# keyfinal.net
KiCad netlist of a schematic drawn in EAGLE
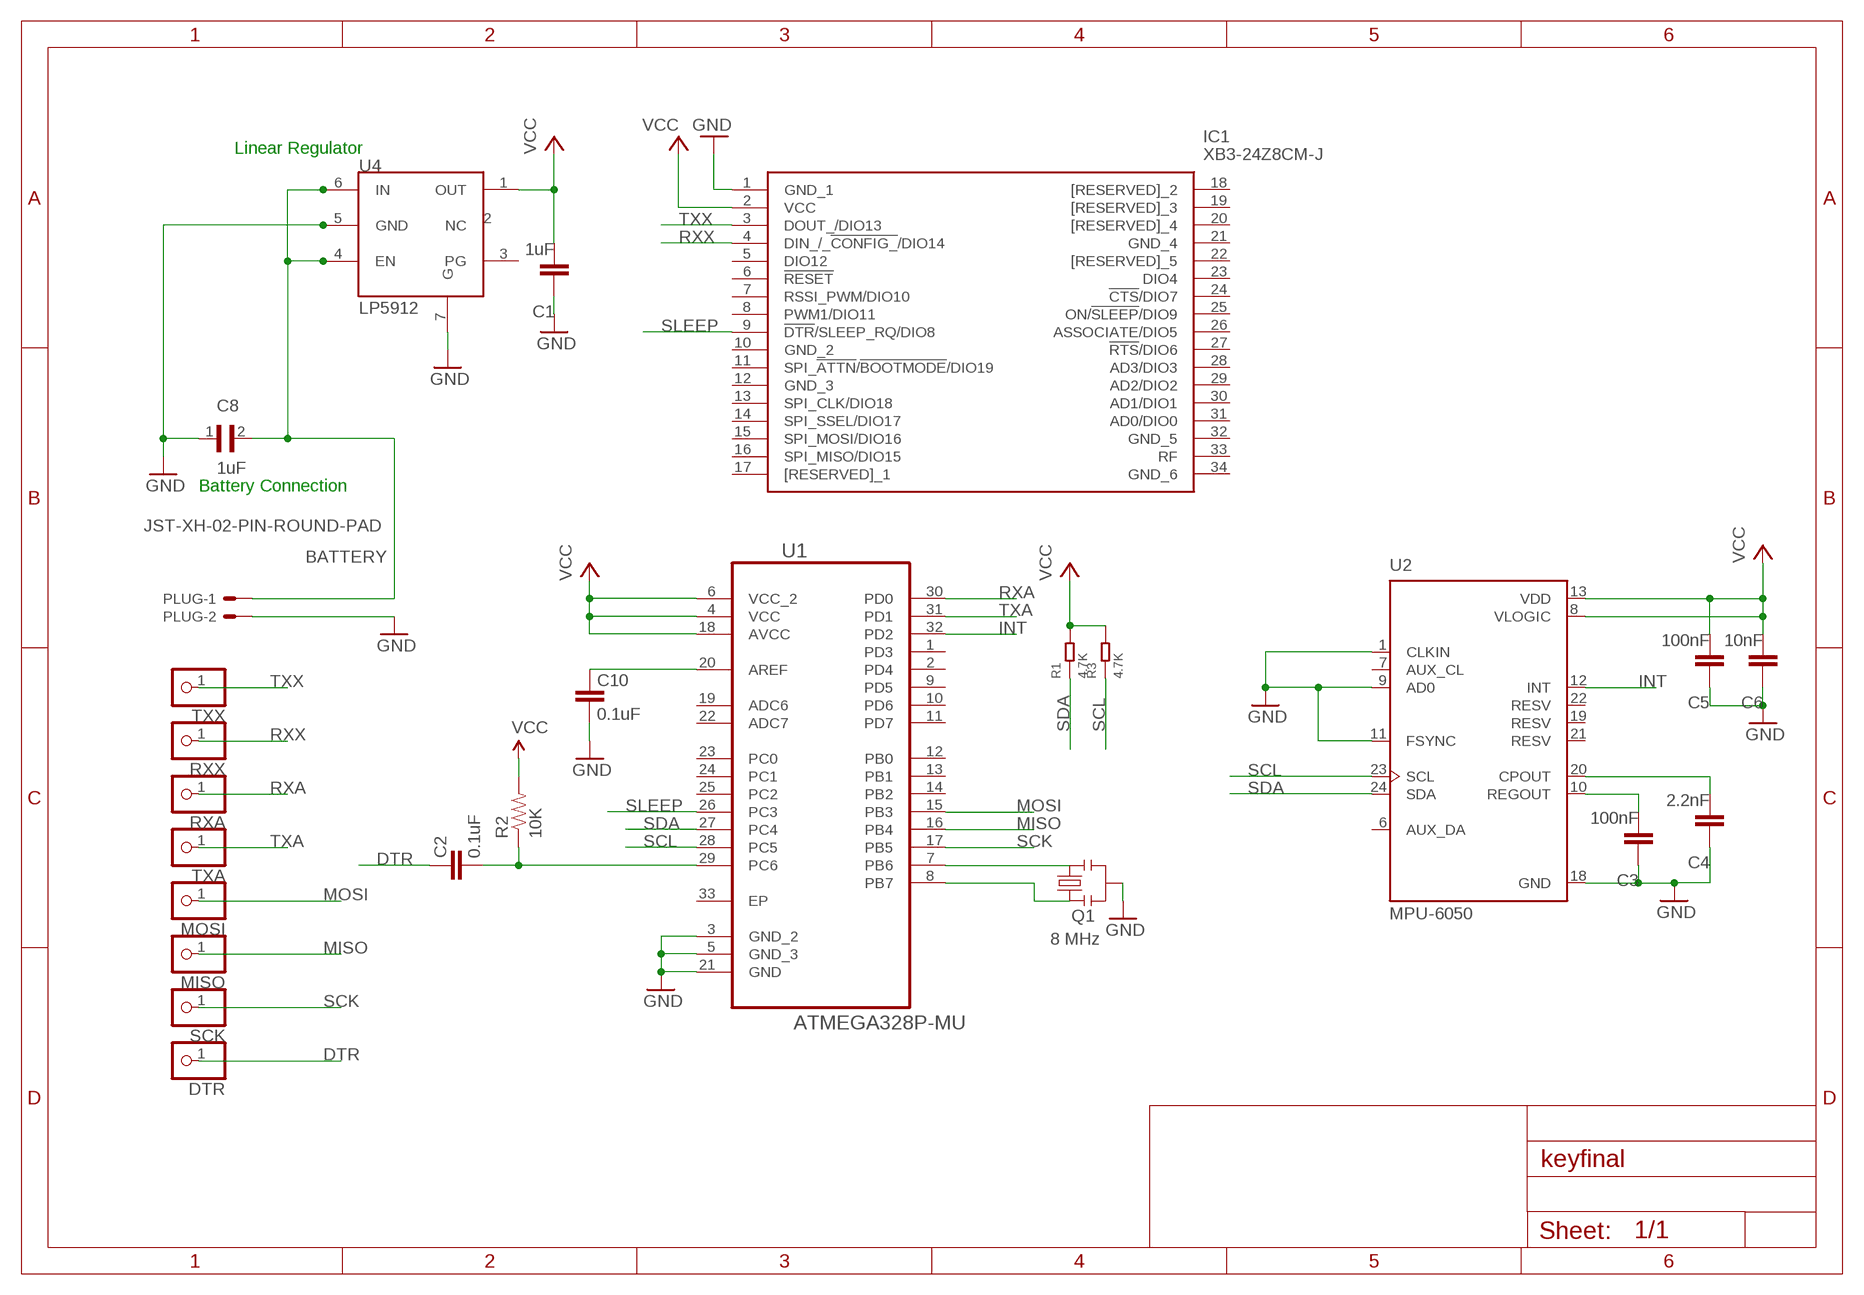
[diagram p0: schematic, sheet 1]

(export (version "E")
  (design (tool "Eeschema 10.0.6"))
  (components
    (comp (ref "C1")
      (value "1uF")
      (footprint "eagle-import:C0603")
      (libsource (lib "eagle-import") (part "C-EUC0603"))
    )
    (comp (ref "C2")
      (value "0.1uF")
      (footprint "eagle-import:0603-CAP")
      (libsource (lib "eagle-import") (part "CAP0603-CAP"))
    )
    (comp (ref "C3")
      (value "100nF")
      (footprint "eagle-import:C0603")
      (libsource (lib "eagle-import") (part "C-EUC0603"))
    )
    (comp (ref "C4")
      (value "2.2nF")
      (footprint "eagle-import:C0603")
      (libsource (lib "eagle-import") (part "C-EUC0603"))
    )
    (comp (ref "C5")
      (value "100nF")
      (footprint "eagle-import:C0603")
      (libsource (lib "eagle-import") (part "C-EUC0603"))
    )
    (comp (ref "C6")
      (value "10nF")
      (footprint "eagle-import:C0603")
      (libsource (lib "eagle-import") (part "C-EUC0603"))
    )
    (comp (ref "C8")
      (value "1uF")
      (footprint "eagle-import:CAPC1005X71N")
      (fields (field (name "MF") "AVX") (field (name "MP") "0402YD105MAT2A"))
      (libsource (lib "eagle-import") (part "0402YD105MAT2A"))
    )
    (comp (ref "C10")
      (value "0.1uF")
      (footprint "eagle-import:0603-CAP")
      (libsource (lib "eagle-import") (part "CAP0603-CAP"))
    )
    (comp (ref "DTR")
      (value "DTR")
      (footprint "eagle-import:1X01")
      (libsource (lib "eagle-import") (part "PINHD-1X1"))
    )
    (comp (ref "IC1")
      (value "XB3-24Z8CM-J")
      (footprint "eagle-import:XB324Z8CMJ")
      (fields (field (name "MOUSER_PART_NUMBER") "888-XB3-24Z8CM-J"))
      (libsource (lib "eagle-import") (part "XB3-24Z8CM-J"))
    )
    (comp (ref "MISO")
      (value "PINHD-1X1")
      (footprint "eagle-import:1X01")
      (libsource (lib "eagle-import") (part "PINHD-1X1"))
    )
    (comp (ref "MOSI")
      (value "PINHD-1X1")
      (footprint "eagle-import:1X01")
      (libsource (lib "eagle-import") (part "PINHD-1X1"))
    )
    (comp (ref "PLUG")
      (value "JST-XH-02-PIN-ROUND-PAD")
      (footprint "eagle-import:JST-XH-02-PACKAGE-ROUND-PAD")
      (libsource (lib "eagle-import") (part "JST-XH-02-PIN-ROUND-PAD"))
    )
    (comp (ref "Q1")
      (value "8 MHz")
      (footprint "eagle-import:RESONATOR-SMD-1_1")
      (libsource (lib "eagle-import") (part "RESONATOR1{colon}1"))
    )
    (comp (ref "R1")
      (value "4.7K")
      (footprint "eagle-import:R0402")
      (fields (field (name "MF") "Yageo") (field (name "MP") "RC0402JR074K7L"))
      (libsource (lib "eagle-import") (part "SMD-RES-4.7K-5%-1/16W(0402)"))
    )
    (comp (ref "R2")
      (value "10K")
      (footprint "eagle-import:0603-RES")
      (libsource (lib "eagle-import") (part "RESISTOR0603-RES"))
    )
    (comp (ref "R3")
      (value "4.7K")
      (footprint "eagle-import:R0402")
      (fields (field (name "MF") "Yageo") (field (name "MP") "RC0402JR074K7L"))
      (libsource (lib "eagle-import") (part "SMD-RES-4.7K-5%-1/16W(0402)"))
    )
    (comp (ref "RXA")
      (value "PINHD-1X1")
      (footprint "eagle-import:1X01")
      (libsource (lib "eagle-import") (part "PINHD-1X1"))
    )
    (comp (ref "RXX")
      (value "PINHD-1X1")
      (footprint "eagle-import:1X01")
      (libsource (lib "eagle-import") (part "PINHD-1X1"))
    )
    (comp (ref "SCK")
      (value "PINHD-1X1")
      (footprint "eagle-import:1X01")
      (fields (field (name "SPICEPREFIX") "X"))
      (libsource (lib "eagle-import") (part "PINHD-1X1"))
    )
    (comp (ref "TXA")
      (value "PINHD-1X1")
      (footprint "eagle-import:1X01")
      (libsource (lib "eagle-import") (part "PINHD-1X1"))
    )
    (comp (ref "TXX")
      (value "PINHD-1X1")
      (footprint "eagle-import:1X01")
      (libsource (lib "eagle-import") (part "PINHD-1X1"))
    )
    (comp (ref "U1")
      (value "ATMEGA328P-MU")
      (footprint "eagle-import:QFN50P500X500X100-33N")
      (fields (field (name "MF") "Microchip"))
      (libsource (lib "eagle-import") (part "ATMEGA328P-MU"))
    )
    (comp (ref "U2")
      (value "MPU-6050")
      (footprint "eagle-import:QFN50P400X400X95-24N")
      (fields (field (name "MF") "TDK InvenSense"))
      (libsource (lib "eagle-import") (part "MPU-6050"))
    )
    (comp (ref "U4")
      (value "LP5912")
      (footprint "eagle-import:LP5912")
      (libsource (lib "eagle-import") (part "LP5912"))
    )
  )
  (nets
    (net (code "1") (name "/BATTERY") (class "Default")
      (node (ref "C8") (pin "2") (pinfunction "2_2") (pintype "passive"))
      (node (ref "PLUG") (pin "1") (pinfunction "S_1") (pintype "passive"))
      (node (ref "U4") (pin "4") (pinfunction "EN_4") (pintype "bidirectional"))
      (node (ref "U4") (pin "6") (pinfunction "IN_6") (pintype "power_in"))
    )
    (net (code "2") (name "/DTR") (class "Default")
      (node (ref "C2") (pin "2") (pinfunction "2_2") (pintype "passive"))
      (node (ref "DTR") (pin "1") (pinfunction "1_1") (pintype "passive"))
    )
    (net (code "3") (name "/INT") (class "Default")
      (node (ref "U1") (pin "32") (pinfunction "PD2_32") (pintype "bidirectional"))
      (node (ref "U2") (pin "12") (pinfunction "INT_12") (pintype "output"))
    )
    (net (code "4") (name "/MISO") (class "Default")
      (node (ref "MISO") (pin "1") (pinfunction "1_1") (pintype "passive"))
      (node (ref "U1") (pin "16") (pinfunction "PB4_16") (pintype "bidirectional"))
    )
    (net (code "5") (name "/MOSI") (class "Default")
      (node (ref "MOSI") (pin "1") (pinfunction "1_1") (pintype "passive"))
      (node (ref "U1") (pin "15") (pinfunction "PB3_15") (pintype "bidirectional"))
    )
    (net (code "6") (name "/RXA") (class "Default")
      (node (ref "RXA") (pin "1") (pinfunction "1_1") (pintype "passive"))
      (node (ref "U1") (pin "30") (pinfunction "PD0_30") (pintype "bidirectional"))
    )
    (net (code "7") (name "/RXX") (class "Default")
      (node (ref "IC1") (pin "4") (pinfunction "DIN_/_~{CONFIG_}/DIO14_4") (pintype "bidirectional"))
      (node (ref "RXX") (pin "1") (pinfunction "1_1") (pintype "passive"))
    )
    (net (code "8") (name "/SCK") (class "Default")
      (node (ref "SCK") (pin "1") (pinfunction "1_1") (pintype "passive"))
      (node (ref "U1") (pin "17") (pinfunction "PB5_17") (pintype "bidirectional"))
    )
    (net (code "9") (name "/SCL") (class "Default")
      (node (ref "R3") (pin "1") (pinfunction "1_1") (pintype "passive"))
      (node (ref "U1") (pin "28") (pinfunction "PC5_28") (pintype "bidirectional"))
      (node (ref "U2") (pin "23") (pinfunction "SCL_23") (pintype "input"))
    )
    (net (code "10") (name "/SDA") (class "Default")
      (node (ref "R1") (pin "1") (pinfunction "1_1") (pintype "passive"))
      (node (ref "U1") (pin "27") (pinfunction "PC4_27") (pintype "bidirectional"))
      (node (ref "U2") (pin "24") (pinfunction "SDA_24") (pintype "bidirectional"))
    )
    (net (code "11") (name "/SLEEP") (class "Default")
      (node (ref "IC1") (pin "9") (pinfunction "~{DTR}/SLEEP_RQ/DIO8_9") (pintype "bidirectional"))
      (node (ref "U1") (pin "26") (pinfunction "PC3_26") (pintype "bidirectional"))
    )
    (net (code "12") (name "/TXA") (class "Default")
      (node (ref "TXA") (pin "1") (pinfunction "1_1") (pintype "passive"))
      (node (ref "U1") (pin "31") (pinfunction "PD1_31") (pintype "bidirectional"))
    )
    (net (code "13") (name "/TXX") (class "Default")
      (node (ref "IC1") (pin "3") (pinfunction "DOUT_/DIO13_3") (pintype "bidirectional"))
      (node (ref "TXX") (pin "1") (pinfunction "1_1") (pintype "passive"))
    )
    (net (code "14") (name "GND") (class "Default")
      (node (ref "C1") (pin "1") (pinfunction "1_1") (pintype "passive"))
      (node (ref "C10") (pin "1") (pinfunction "1_1") (pintype "passive"))
      (node (ref "C3") (pin "1") (pinfunction "1_1") (pintype "passive"))
      (node (ref "C4") (pin "1") (pinfunction "1_1") (pintype "passive"))
      (node (ref "C5") (pin "1") (pinfunction "1_1") (pintype "passive"))
      (node (ref "C6") (pin "1") (pinfunction "1_1") (pintype "passive"))
      (node (ref "C8") (pin "1") (pinfunction "1_1") (pintype "passive"))
      (node (ref "IC1") (pin "1") (pinfunction "GND_1_1") (pintype "bidirectional"))
      (node (ref "PLUG") (pin "2") (pinfunction "S_2") (pintype "passive"))
      (node (ref "Q1") (pin "2") (pinfunction "2_2") (pintype "passive"))
      (node (ref "U1") (pin "21") (pinfunction "GND_21") (pintype "passive"))
      (node (ref "U1") (pin "3") (pinfunction "GND_2_3") (pintype "passive"))
      (node (ref "U1") (pin "5") (pinfunction "GND_3_5") (pintype "passive"))
      (node (ref "U2") (pin "1") (pinfunction "CLKIN_1") (pintype "input"))
      (node (ref "U2") (pin "11") (pinfunction "FSYNC_11") (pintype "input"))
      (node (ref "U2") (pin "18") (pinfunction "GND_18") (pintype "power_in"))
      (node (ref "U2") (pin "9") (pinfunction "AD0_9") (pintype "input"))
      (node (ref "U4") (pin "5") (pinfunction "GND_5") (pintype "power_in"))
      (node (ref "U4") (pin "7") (pinfunction "G_7") (pintype "bidirectional"))
    )
    (net (code "15") (name "Net-(U1-AREF)") (class "Default")
      (node (ref "C10") (pin "2") (pinfunction "2_2") (pintype "passive"))
      (node (ref "U1") (pin "20") (pinfunction "AREF_20") (pintype "input"))
    )
    (net (code "16") (name "Net-(U1-PB6)") (class "Default")
      (node (ref "Q1") (pin "3") (pinfunction "3_3") (pintype "passive"))
      (node (ref "U1") (pin "7") (pinfunction "PB6_7") (pintype "bidirectional"))
    )
    (net (code "17") (name "Net-(U1-PB7)") (class "Default")
      (node (ref "Q1") (pin "1") (pinfunction "1_1") (pintype "passive"))
      (node (ref "U1") (pin "8") (pinfunction "PB7_8") (pintype "bidirectional"))
    )
    (net (code "18") (name "Net-(U1-PC6)") (class "Default")
      (node (ref "C2") (pin "1") (pinfunction "1_1") (pintype "passive"))
      (node (ref "R2") (pin "1") (pinfunction "1_1") (pintype "passive"))
      (node (ref "U1") (pin "29") (pinfunction "PC6_29") (pintype "bidirectional"))
    )
    (net (code "19") (name "Net-(U2-CPOUT)") (class "Default")
      (node (ref "C4") (pin "2") (pinfunction "2_2") (pintype "passive"))
      (node (ref "U2") (pin "20") (pinfunction "CPOUT_20") (pintype "passive"))
    )
    (net (code "20") (name "Net-(U2-REGOUT)") (class "Default")
      (node (ref "C3") (pin "2") (pinfunction "2_2") (pintype "passive"))
      (node (ref "U2") (pin "10") (pinfunction "REGOUT_10") (pintype "passive"))
    )
    (net (code "21") (name "VCC") (class "Default")
      (node (ref "C1") (pin "2") (pinfunction "2_2") (pintype "passive"))
      (node (ref "C5") (pin "2") (pinfunction "2_2") (pintype "passive"))
      (node (ref "C6") (pin "2") (pinfunction "2_2") (pintype "passive"))
      (node (ref "IC1") (pin "2") (pinfunction "VCC_2") (pintype "bidirectional"))
      (node (ref "R1") (pin "2") (pinfunction "2_2") (pintype "passive"))
      (node (ref "R2") (pin "2") (pinfunction "2_2") (pintype "passive"))
      (node (ref "R3") (pin "2") (pinfunction "2_2") (pintype "passive"))
      (node (ref "U1") (pin "18") (pinfunction "AVCC_18") (pintype "power_in"))
      (node (ref "U1") (pin "4") (pinfunction "VCC_4") (pintype "power_in"))
      (node (ref "U1") (pin "6") (pinfunction "VCC_2_6") (pintype "power_in"))
      (node (ref "U2") (pin "13") (pinfunction "VDD_13") (pintype "power_in"))
      (node (ref "U2") (pin "8") (pinfunction "VLOGIC_8") (pintype "power_in"))
      (node (ref "U4") (pin "1") (pinfunction "OUT_1") (pintype "power_in"))
    )
    (net (code "22") (name "unconnected-(IC1-AD0{slash}DIO0-Pad31)") (class "Default")
      (node (ref "IC1") (pin "31") (pinfunction "AD0/DIO0_31") (pintype "bidirectional"))
    )
    (net (code "23") (name "unconnected-(IC1-AD1{slash}DIO1-Pad30)") (class "Default")
      (node (ref "IC1") (pin "30") (pinfunction "AD1/DIO1_30") (pintype "bidirectional"))
    )
    (net (code "24") (name "unconnected-(IC1-AD2{slash}DIO2-Pad29)") (class "Default")
      (node (ref "IC1") (pin "29") (pinfunction "AD2/DIO2_29") (pintype "bidirectional"))
    )
    (net (code "25") (name "unconnected-(IC1-AD3{slash}DIO3-Pad28)") (class "Default")
      (node (ref "IC1") (pin "28") (pinfunction "AD3/DIO3_28") (pintype "bidirectional"))
    )
    (net (code "26") (name "unconnected-(IC1-ASSOCIATE{slash}DIO5-Pad26)") (class "Default")
      (node (ref "IC1") (pin "26") (pinfunction "ASSOCIATE/DIO5_26") (pintype "bidirectional"))
    )
    (net (code "27") (name "unconnected-(IC1-DIO4-Pad23)") (class "Default")
      (node (ref "IC1") (pin "23") (pinfunction "DIO4_23") (pintype "bidirectional"))
    )
    (net (code "28") (name "unconnected-(IC1-DIO12-Pad5)") (class "Default")
      (node (ref "IC1") (pin "5") (pinfunction "DIO12_5") (pintype "bidirectional"))
    )
    (net (code "29") (name "unconnected-(IC1-GND_2-Pad10)") (class "Default")
      (node (ref "IC1") (pin "10") (pinfunction "GND_2_10") (pintype "bidirectional"))
    )
    (net (code "30") (name "unconnected-(IC1-GND_3-Pad12)") (class "Default")
      (node (ref "IC1") (pin "12") (pinfunction "GND_3_12") (pintype "bidirectional"))
    )
    (net (code "31") (name "unconnected-(IC1-GND_4-Pad21)") (class "Default")
      (node (ref "IC1") (pin "21") (pinfunction "GND_4_21") (pintype "bidirectional"))
    )
    (net (code "32") (name "unconnected-(IC1-GND_5-Pad32)") (class "Default")
      (node (ref "IC1") (pin "32") (pinfunction "GND_5_32") (pintype "bidirectional"))
    )
    (net (code "33") (name "unconnected-(IC1-GND_6-Pad34)") (class "Default")
      (node (ref "IC1") (pin "34") (pinfunction "GND_6_34") (pintype "bidirectional"))
    )
    (net (code "34") (name "unconnected-(IC1-ON{slash}~{SLEEP}{slash}DIO9-Pad25)") (class "Default")
      (node (ref "IC1") (pin "25") (pinfunction "ON/~{SLEEP}/DIO9_25") (pintype "bidirectional"))
    )
    (net (code "35") (name "unconnected-(IC1-PWM1{slash}DIO11-Pad8)") (class "Default")
      (node (ref "IC1") (pin "8") (pinfunction "PWM1/DIO11_8") (pintype "bidirectional"))
    )
    (net (code "36") (name "unconnected-(IC1-RF-Pad33)") (class "Default")
      (node (ref "IC1") (pin "33") (pinfunction "RF_33") (pintype "bidirectional"))
    )
    (net (code "37") (name "unconnected-(IC1-RSSI_PWM{slash}DIO10-Pad7)") (class "Default")
      (node (ref "IC1") (pin "7") (pinfunction "RSSI_PWM/DIO10_7") (pintype "bidirectional"))
    )
    (net (code "38") (name "unconnected-(IC1-SPI_CLK{slash}DIO18-Pad13)") (class "Default")
      (node (ref "IC1") (pin "13") (pinfunction "SPI_CLK/DIO18_13") (pintype "bidirectional"))
    )
    (net (code "39") (name "unconnected-(IC1-SPI_MISO{slash}DIO15-Pad16)") (class "Default")
      (node (ref "IC1") (pin "16") (pinfunction "SPI_MISO/DIO15_16") (pintype "bidirectional"))
    )
    (net (code "40") (name "unconnected-(IC1-SPI_MOSI{slash}DIO16-Pad15)") (class "Default")
      (node (ref "IC1") (pin "15") (pinfunction "SPI_MOSI/DIO16_15") (pintype "bidirectional"))
    )
    (net (code "41") (name "unconnected-(IC1-SPI_SSEL{slash}DIO17-Pad14)") (class "Default")
      (node (ref "IC1") (pin "14") (pinfunction "SPI_SSEL/DIO17_14") (pintype "bidirectional"))
    )
    (net (code "42") (name "unconnected-(IC1-SPI_~{ATTN}{slash}~{BOOTMODE}{slash}DIO19-Pad11)") (class "Default")
      (node (ref "IC1") (pin "11") (pinfunction "SPI_~{ATTN}/~{BOOTMODE}/DIO19_11") (pintype "bidirectional"))
    )
    (net (code "43") (name "unconnected-(IC1-[RESERVED]_1-Pad17)") (class "Default")
      (node (ref "IC1") (pin "17") (pinfunction "[RESERVED]_1_17") (pintype "bidirectional"))
    )
    (net (code "44") (name "unconnected-(IC1-[RESERVED]_2-Pad18)") (class "Default")
      (node (ref "IC1") (pin "18") (pinfunction "[RESERVED]_2_18") (pintype "bidirectional"))
    )
    (net (code "45") (name "unconnected-(IC1-[RESERVED]_3-Pad19)") (class "Default")
      (node (ref "IC1") (pin "19") (pinfunction "[RESERVED]_3_19") (pintype "bidirectional"))
    )
    (net (code "46") (name "unconnected-(IC1-[RESERVED]_4-Pad20)") (class "Default")
      (node (ref "IC1") (pin "20") (pinfunction "[RESERVED]_4_20") (pintype "bidirectional"))
    )
    (net (code "47") (name "unconnected-(IC1-[RESERVED]_5-Pad22)") (class "Default")
      (node (ref "IC1") (pin "22") (pinfunction "[RESERVED]_5_22") (pintype "bidirectional"))
    )
    (net (code "48") (name "unconnected-(IC1-~{CTS}{slash}DIO7-Pad24)") (class "Default")
      (node (ref "IC1") (pin "24") (pinfunction "~{CTS}/DIO7_24") (pintype "bidirectional"))
    )
    (net (code "49") (name "unconnected-(IC1-~{RESET}-Pad6)") (class "Default")
      (node (ref "IC1") (pin "6") (pinfunction "~{RESET}_6") (pintype "bidirectional"))
    )
    (net (code "50") (name "unconnected-(IC1-~{RTS}{slash}DIO6-Pad27)") (class "Default")
      (node (ref "IC1") (pin "27") (pinfunction "~{RTS}/DIO6_27") (pintype "bidirectional"))
    )
    (net (code "51") (name "unconnected-(U1-ADC6-Pad19)") (class "Default")
      (node (ref "U1") (pin "19") (pinfunction "ADC6_19") (pintype "input"))
    )
    (net (code "52") (name "unconnected-(U1-ADC7-Pad22)") (class "Default")
      (node (ref "U1") (pin "22") (pinfunction "ADC7_22") (pintype "input"))
    )
    (net (code "53") (name "unconnected-(U1-EP-Pad33)") (class "Default")
      (node (ref "U1") (pin "33") (pinfunction "EP_33") (pintype "passive"))
    )
    (net (code "54") (name "unconnected-(U1-PB0-Pad12)") (class "Default")
      (node (ref "U1") (pin "12") (pinfunction "PB0_12") (pintype "bidirectional"))
    )
    (net (code "55") (name "unconnected-(U1-PB1-Pad13)") (class "Default")
      (node (ref "U1") (pin "13") (pinfunction "PB1_13") (pintype "bidirectional"))
    )
    (net (code "56") (name "unconnected-(U1-PB2-Pad14)") (class "Default")
      (node (ref "U1") (pin "14") (pinfunction "PB2_14") (pintype "bidirectional"))
    )
    (net (code "57") (name "unconnected-(U1-PC0-Pad23)") (class "Default")
      (node (ref "U1") (pin "23") (pinfunction "PC0_23") (pintype "bidirectional"))
    )
    (net (code "58") (name "unconnected-(U1-PC1-Pad24)") (class "Default")
      (node (ref "U1") (pin "24") (pinfunction "PC1_24") (pintype "bidirectional"))
    )
    (net (code "59") (name "unconnected-(U1-PC2-Pad25)") (class "Default")
      (node (ref "U1") (pin "25") (pinfunction "PC2_25") (pintype "bidirectional"))
    )
    (net (code "60") (name "unconnected-(U1-PD3-Pad1)") (class "Default")
      (node (ref "U1") (pin "1") (pinfunction "PD3_1") (pintype "bidirectional"))
    )
    (net (code "61") (name "unconnected-(U1-PD4-Pad2)") (class "Default")
      (node (ref "U1") (pin "2") (pinfunction "PD4_2") (pintype "bidirectional"))
    )
    (net (code "62") (name "unconnected-(U1-PD5-Pad9)") (class "Default")
      (node (ref "U1") (pin "9") (pinfunction "PD5_9") (pintype "bidirectional"))
    )
    (net (code "63") (name "unconnected-(U1-PD6-Pad10)") (class "Default")
      (node (ref "U1") (pin "10") (pinfunction "PD6_10") (pintype "bidirectional"))
    )
    (net (code "64") (name "unconnected-(U1-PD7-Pad11)") (class "Default")
      (node (ref "U1") (pin "11") (pinfunction "PD7_11") (pintype "bidirectional"))
    )
    (net (code "65") (name "unconnected-(U2-AUX_CL-Pad7)") (class "Default")
      (node (ref "U2") (pin "7") (pinfunction "AUX_CL_7") (pintype "input"))
    )
    (net (code "66") (name "unconnected-(U2-AUX_DA-Pad6)") (class "Default")
      (node (ref "U2") (pin "6") (pinfunction "AUX_DA_6") (pintype "bidirectional"))
    )
    (net (code "67") (name "unconnected-(U2-RESV-Pad19)") (class "Default")
      (node (ref "U2") (pin "19") (pinfunction "RESV_19") (pintype "passive"))
    )
    (net (code "68") (name "unconnected-(U2-RESV-Pad21)") (class "Default")
      (node (ref "U2") (pin "21") (pinfunction "RESV_21") (pintype "passive"))
    )
    (net (code "69") (name "unconnected-(U2-RESV-Pad22)") (class "Default")
      (node (ref "U2") (pin "22") (pinfunction "RESV_22") (pintype "passive"))
    )
    (net (code "70") (name "unconnected-(U4-NC-Pad2)") (class "Default")
      (node (ref "U4") (pin "2") (pinfunction "NC_2") (pintype "bidirectional"))
    )
    (net (code "71") (name "unconnected-(U4-PG-Pad3)") (class "Default")
      (node (ref "U4") (pin "3") (pinfunction "PG_3") (pintype "bidirectional"))
    )
  )
)
